# current_sense.net
KiCad netlist of a schematic drawn in EAGLE
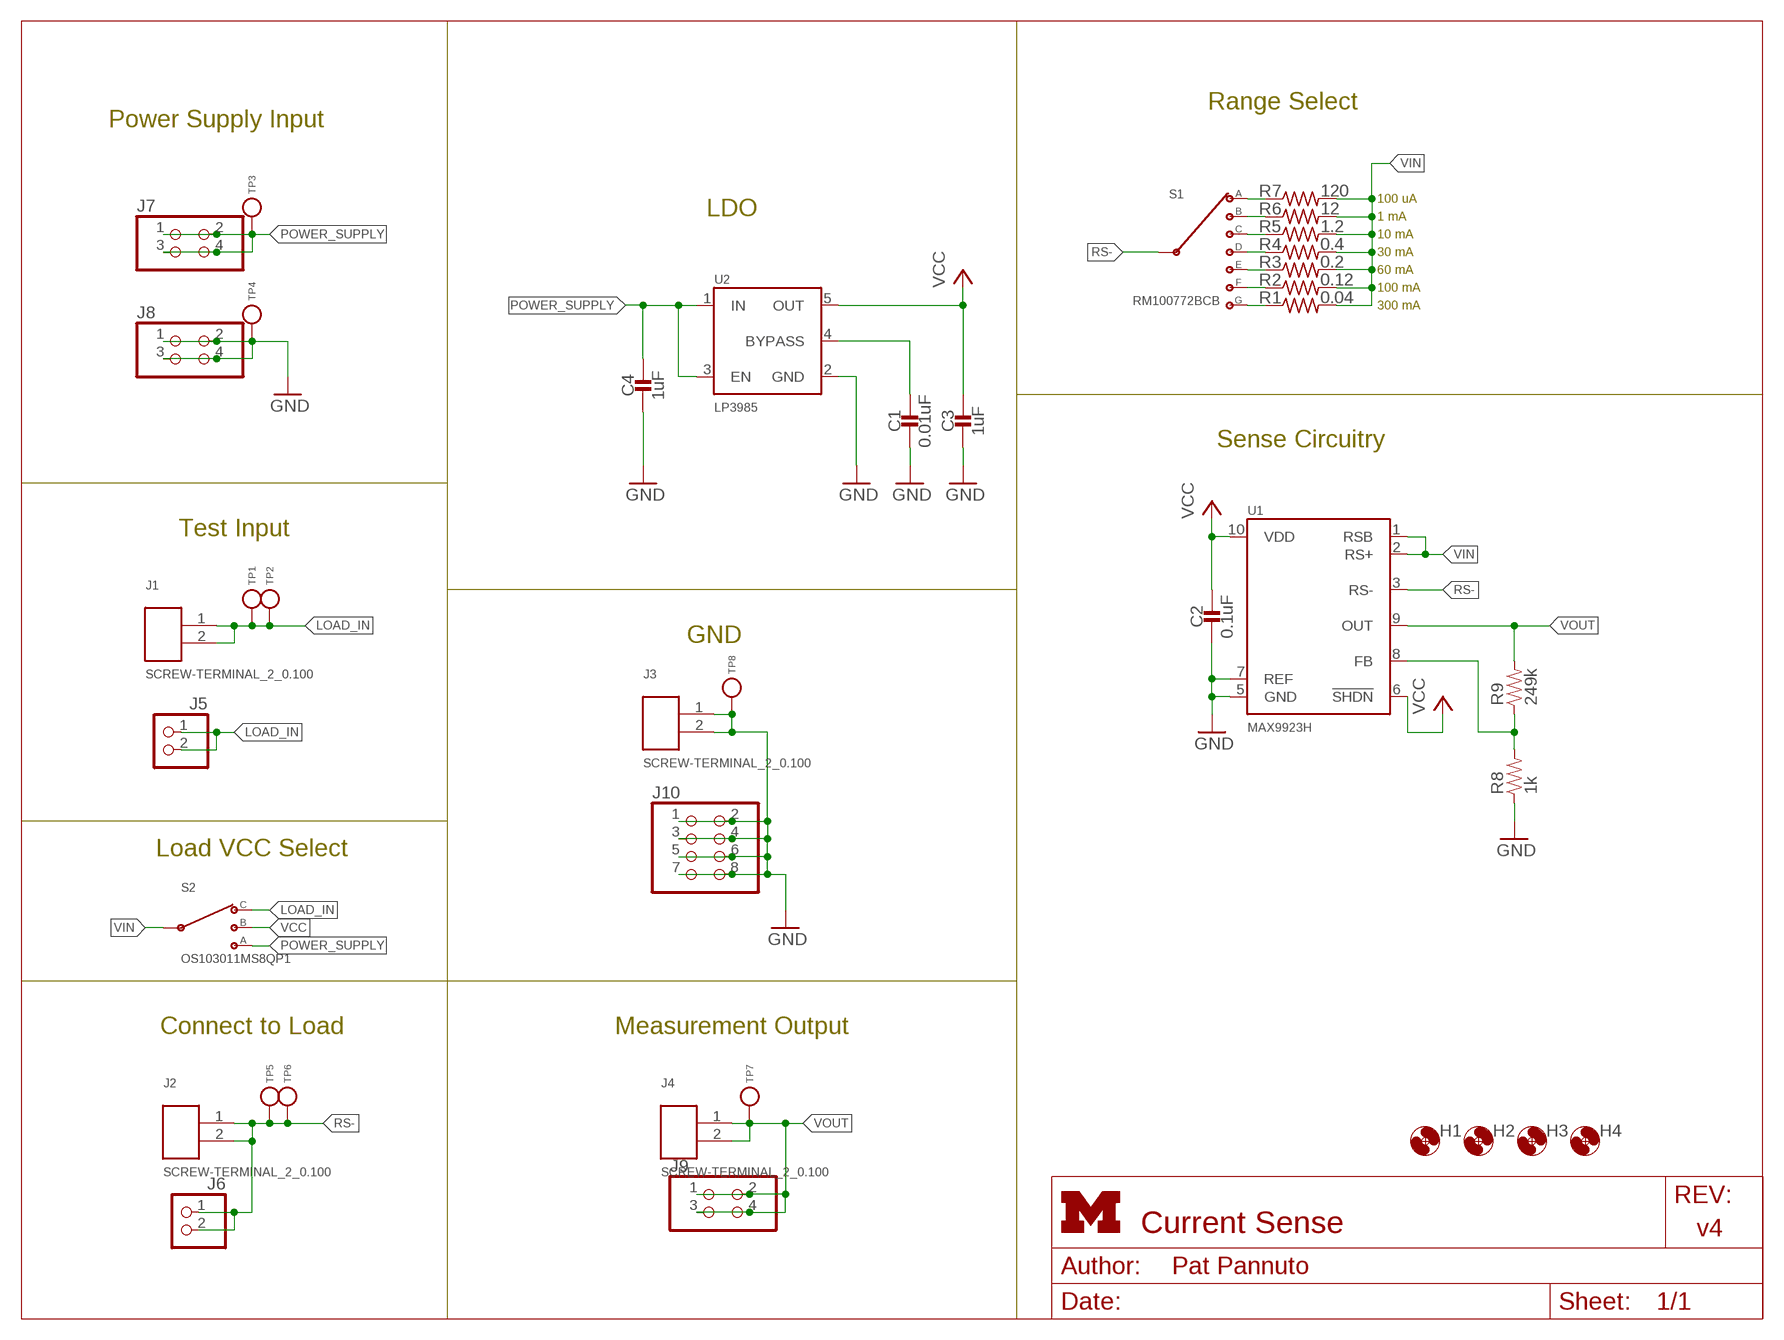
[diagram p0: schematic, sheet 1]

(export (version "E")
  (design (tool "Eeschema 10.0.6"))
  (components
    (comp (ref "C1")
      (value "0.01uF")
      (footprint "eagle-import:0603_CAP")
      (description "CAP CER 10000PF 25V X7R 0603")
      (fields (field (name "MANUFACTURER") "TDK") (field (name "MPN") "C1608X7R1E103K080AA"))
      (libsource (lib "eagle-import") (part "CAPACITOR0603_CAP"))
    )
    (comp (ref "C2")
      (value "0.1uF")
      (footprint "eagle-import:0603_CAP")
      (description "CAP CER .10UF 25V X7R 10% 0603")
      (fields (field (name "MANUFACTURER") "TDK") (field (name "MPN") "C1608X7R1E104K080AA"))
      (libsource (lib "eagle-import") (part "CAPACITOR0603_CAP"))
    )
    (comp (ref "C3")
      (value "1uF")
      (footprint "eagle-import:0603_CAP")
      (description "CAP CER 1UF 16V X7R 0603")
      (fields (field (name "MANUFACTURER") "TDK") (field (name "MPN") "C1608X7R1C105K080AC"))
      (libsource (lib "eagle-import") (part "CAPACITOR0603_CAP"))
    )
    (comp (ref "C4")
      (value "1uF")
      (footprint "eagle-import:0603_CAP")
      (description "CAP CER 1UF 16V X7R 0603")
      (fields (field (name "MANUFACTURER") "TDK") (field (name "MPN") "C1608X7R1C105K080AC"))
      (libsource (lib "eagle-import") (part "CAPACITOR0603_CAP"))
    )
    (comp (ref "H1")
      (value "MOUNT-HOLE3.2")
      (footprint "eagle-import:3,2")
      (libsource (lib "eagle-import") (part "MOUNT-HOLE3.2"))
    )
    (comp (ref "H2")
      (value "MOUNT-HOLE3.2")
      (footprint "eagle-import:3,2")
      (libsource (lib "eagle-import") (part "MOUNT-HOLE3.2"))
    )
    (comp (ref "H3")
      (value "MOUNT-HOLE3.2")
      (footprint "eagle-import:3,2")
      (libsource (lib "eagle-import") (part "MOUNT-HOLE3.2"))
    )
    (comp (ref "H4")
      (value "MOUNT-HOLE3.2")
      (footprint "eagle-import:3,2")
      (libsource (lib "eagle-import") (part "MOUNT-HOLE3.2"))
    )
    (comp (ref "J1")
      (value "SCREW-TERMINAL_2_0.100")
      (footprint "eagle-import:CONN_BLOCK_2")
      (libsource (lib "eagle-import") (part "SCREW-TERMINAL_2_0.100"))
    )
    (comp (ref "J2")
      (value "SCREW-TERMINAL_2_0.100")
      (footprint "eagle-import:CONN_BLOCK_2")
      (libsource (lib "eagle-import") (part "SCREW-TERMINAL_2_0.100"))
    )
    (comp (ref "J3")
      (value "SCREW-TERMINAL_2_0.100")
      (footprint "eagle-import:CONN_BLOCK_2")
      (libsource (lib "eagle-import") (part "SCREW-TERMINAL_2_0.100"))
    )
    (comp (ref "J4")
      (value "SCREW-TERMINAL_2_0.100")
      (footprint "eagle-import:CONN_BLOCK_2")
      (libsource (lib "eagle-import") (part "SCREW-TERMINAL_2_0.100"))
    )
    (comp (ref "J5")
      (value "PINHD-1X2")
      (footprint "eagle-import:1X02")
      (libsource (lib "eagle-import") (part "PINHD-1X2"))
    )
    (comp (ref "J6")
      (value "PINHD-1X2")
      (footprint "eagle-import:1X02")
      (libsource (lib "eagle-import") (part "PINHD-1X2"))
    )
    (comp (ref "J7")
      (value "PINHD-2X2")
      (footprint "eagle-import:2X02")
      (libsource (lib "eagle-import") (part "PINHD-2X2"))
    )
    (comp (ref "J8")
      (value "PINHD-2X2")
      (footprint "eagle-import:2X02")
      (libsource (lib "eagle-import") (part "PINHD-2X2"))
    )
    (comp (ref "J9")
      (value "PINHD-2X2")
      (footprint "eagle-import:2X02")
      (libsource (lib "eagle-import") (part "PINHD-2X2"))
    )
    (comp (ref "J10")
      (value "PINHD-2X4")
      (footprint "eagle-import:2X04")
      (libsource (lib "eagle-import") (part "PINHD-2X4"))
    )
    (comp (ref "R1")
      (value "0.04")
      (footprint "eagle-import:R1206")
      (description "RES 0.04 OHM 1% 1/4W 1206")
      (fields (field (name "MANUFACTURER") "Yageo") (field (name "MPN") "RL1206FR-070R04L"))
      (libsource (lib "eagle-import") (part "R-US_R1206"))
    )
    (comp (ref "R2")
      (value "0.12")
      (footprint "eagle-import:R1206")
      (description "RES 0.12 OHM 1% 1/2W 1206")
      (fields (field (name "MANUFACTURER") "Susumu") (field (name "MPN") "RL1632R-R120-F"))
      (libsource (lib "eagle-import") (part "R-US_R1206"))
    )
    (comp (ref "R3")
      (value "0.2")
      (footprint "eagle-import:R1206")
      (description "RES 0.2 OHM 1% 1/2W 1206")
      (fields (field (name "MANUFACTURER") "Stackpole Electronics") (field (name "MPN") "CSR1206FKR200"))
      (libsource (lib "eagle-import") (part "R-US_R1206"))
    )
    (comp (ref "R4")
      (value "0.4")
      (footprint "eagle-import:R1206")
      (description "RES 0.4 OHM 1% 1/4W 1206")
      (fields (field (name "MANUFACTURER") "Yageo") (field (name "MPN") "RL1206FR-070R4L"))
      (libsource (lib "eagle-import") (part "R-US_R1206"))
    )
    (comp (ref "R5")
      (value "1.2")
      (footprint "eagle-import:R0805")
      (description "RES SMD 1.2 OHM 1% 1/3W 0805")
      (fields (field (name "MANUFACTURER") "Susumu") (field (name "MPN") "RL1220S-1R2-F"))
      (libsource (lib "eagle-import") (part "R-US_R0805"))
    )
    (comp (ref "R6")
      (value "12")
      (footprint "eagle-import:R0805")
      (description "RES SMD 12 OHM 0.1% 1/10W 0805")
      (fields (field (name "MANUFACTURER") "TE Connectivity") (field (name "MPN") "CPF0805B12RE1"))
      (libsource (lib "eagle-import") (part "R-US_R0805"))
    )
    (comp (ref "R7")
      (value "120")
      (footprint "eagle-import:R0805")
      (description "RES SMD 120 OHM 0.05% 1/8W 0805")
      (fields (field (name "MANUFACTURER") "Susumu") (field (name "MPN") "RG2012N-121-W-T1"))
      (libsource (lib "eagle-import") (part "R-US_R0805"))
    )
    (comp (ref "R8")
      (value "1k")
      (footprint "eagle-import:0603-RES")
      (description "RES 1.0K OHM 1/10W .1% 0603 SMD")
      (fields (field (name "MANUFACTURER") "Panasonic") (field (name "MPN") "ERA-3AEB102V"))
      (libsource (lib "eagle-import") (part "RESISTOR0603_RES"))
    )
    (comp (ref "R9")
      (value "249k")
      (footprint "eagle-import:0603-RES")
      (description "RES 249K OHM 1/10W .1% 0603 SMD")
      (fields (field (name "MANUFACTURER") "Panasonic") (field (name "MPN") "ERA-3AEB2493V"))
      (libsource (lib "eagle-import") (part "RESISTOR0603_RES"))
    )
    (comp (ref "S1")
      (value "RM100772BCB")
      (footprint "eagle-import:RM-SWITCH")
      (description "SWITCH ROTARY 7POS 500MA 24V")
      (fields (field (name "MANUFACTURER") "C&K Components") (field (name "MPN") "RM107772BCB"))
      (libsource (lib "eagle-import") (part "RM100772BCB"))
    )
    (comp (ref "S2")
      (value "OS103011MS8QP1")
      (footprint "eagle-import:OS102011MS8QP1")
      (libsource (lib "eagle-import") (part "OS103011MS8QP1"))
    )
    (comp (ref "TP1")
      (value "TEST_POINT_0.040IN")
      (footprint "eagle-import:TESTPOINT_0.040IN")
      (libsource (lib "eagle-import") (part "TEST_POINT_0.040IN"))
    )
    (comp (ref "TP2")
      (value "TEST_POINT_0.040IN")
      (footprint "eagle-import:TESTPOINT_0.040IN")
      (libsource (lib "eagle-import") (part "TEST_POINT_0.040IN"))
    )
    (comp (ref "TP3")
      (value "TEST_POINT_0.040IN")
      (footprint "eagle-import:TESTPOINT_0.040IN")
      (libsource (lib "eagle-import") (part "TEST_POINT_0.040IN"))
    )
    (comp (ref "TP4")
      (value "TEST_POINT_0.040IN")
      (footprint "eagle-import:TESTPOINT_0.040IN")
      (libsource (lib "eagle-import") (part "TEST_POINT_0.040IN"))
    )
    (comp (ref "TP5")
      (value "TEST_POINT_0.040IN")
      (footprint "eagle-import:TESTPOINT_0.040IN")
      (libsource (lib "eagle-import") (part "TEST_POINT_0.040IN"))
    )
    (comp (ref "TP6")
      (value "TEST_POINT_0.040IN")
      (footprint "eagle-import:TESTPOINT_0.040IN")
      (libsource (lib "eagle-import") (part "TEST_POINT_0.040IN"))
    )
    (comp (ref "TP7")
      (value "TEST_POINT_0.040IN")
      (footprint "eagle-import:TESTPOINT_0.040IN")
      (libsource (lib "eagle-import") (part "TEST_POINT_0.040IN"))
    )
    (comp (ref "TP8")
      (value "TEST_POINT_0.112IN")
      (footprint "eagle-import:TESTPOINT_0.112IN")
      (libsource (lib "eagle-import") (part "TEST_POINT_0.112IN"))
    )
    (comp (ref "U1")
      (value "MAX9923H")
      (footprint "eagle-import:UMAX10")
      (description "IC AMP CURRENT SENSE 10-MSOP")
      (fields
        (field (name "DIGIKEY") "MAX9922EUB+TCT-ND")
        (field (name "MANUFACTURER") "Maxim Integrated")
        (field (name "MPN") "MAX9922EUB+T")
      )
      (libsource (lib "eagle-import") (part "MAX9923H"))
    )
    (comp (ref "U2")
      (value "LP3985")
      (footprint "eagle-import:R-PDSO-G5")
      (libsource (lib "eagle-import") (part "LP3985"))
    )
  )
  (nets
    (net (code "1") (name "GND") (class "Default")
      (node (ref "C1") (pin "2") (pinfunction "2_2") (pintype "bidirectional"))
      (node (ref "C2") (pin "2") (pinfunction "2_2") (pintype "bidirectional"))
      (node (ref "C3") (pin "2") (pinfunction "2_2") (pintype "bidirectional"))
      (node (ref "C4") (pin "2") (pinfunction "2_2") (pintype "bidirectional"))
      (node (ref "J10") (pin "1") (pinfunction "1_1") (pintype "passive"))
      (node (ref "J10") (pin "2") (pinfunction "2_2") (pintype "passive"))
      (node (ref "J10") (pin "3") (pinfunction "3_3") (pintype "passive"))
      (node (ref "J10") (pin "4") (pinfunction "4_4") (pintype "passive"))
      (node (ref "J10") (pin "5") (pinfunction "5_5") (pintype "passive"))
      (node (ref "J10") (pin "6") (pinfunction "6_6") (pintype "passive"))
      (node (ref "J10") (pin "7") (pinfunction "7_7") (pintype "passive"))
      (node (ref "J10") (pin "8") (pinfunction "8_8") (pintype "passive"))
      (node (ref "J3") (pin "1") (pinfunction "1_1") (pintype "bidirectional"))
      (node (ref "J3") (pin "2") (pinfunction "2_2") (pintype "bidirectional"))
      (node (ref "J8") (pin "1") (pinfunction "1_1") (pintype "passive"))
      (node (ref "J8") (pin "2") (pinfunction "2_2") (pintype "passive"))
      (node (ref "J8") (pin "3") (pinfunction "3_3") (pintype "passive"))
      (node (ref "J8") (pin "4") (pinfunction "4_4") (pintype "passive"))
      (node (ref "R8") (pin "1") (pinfunction "1_1") (pintype "passive"))
      (node (ref "TP4") (pin "TESTPOINT") (pinfunction "TESTPOINT_TESTPOINT") (pintype "bidirectional"))
      (node (ref "TP8") (pin "1") (pinfunction "TESTPOINT_1") (pintype "bidirectional"))
      (node (ref "U1") (pin "5") (pinfunction "GND_5") (pintype "bidirectional"))
      (node (ref "U1") (pin "7") (pinfunction "REF_7") (pintype "bidirectional"))
      (node (ref "U2") (pin "2") (pinfunction "GND_2") (pintype "bidirectional"))
    )
    (net (code "2") (name "LOAD_IN") (class "Default")
      (node (ref "J1") (pin "1") (pinfunction "1_1") (pintype "bidirectional"))
      (node (ref "J1") (pin "2") (pinfunction "2_2") (pintype "bidirectional"))
      (node (ref "J5") (pin "1") (pinfunction "1_1") (pintype "passive"))
      (node (ref "J5") (pin "2") (pinfunction "2_2") (pintype "passive"))
      (node (ref "S2") (pin "4") (pinfunction "3_4") (pintype "bidirectional"))
      (node (ref "TP1") (pin "TESTPOINT") (pinfunction "TESTPOINT_TESTPOINT") (pintype "bidirectional"))
      (node (ref "TP2") (pin "TESTPOINT") (pinfunction "TESTPOINT_TESTPOINT") (pintype "bidirectional"))
    )
    (net (code "3") (name "Net-(S1-A)") (class "Default")
      (node (ref "R7") (pin "1") (pinfunction "1_1") (pintype "passive"))
      (node (ref "S1") (pin "1") (pinfunction "A_1") (pintype "bidirectional"))
    )
    (net (code "4") (name "Net-(S1-B)") (class "Default")
      (node (ref "R6") (pin "1") (pinfunction "1_1") (pintype "passive"))
      (node (ref "S1") (pin "2") (pinfunction "B_2") (pintype "bidirectional"))
    )
    (net (code "5") (name "Net-(S1-C)") (class "Default")
      (node (ref "R5") (pin "1") (pinfunction "1_1") (pintype "passive"))
      (node (ref "S1") (pin "3") (pinfunction "C_3") (pintype "bidirectional"))
    )
    (net (code "6") (name "Net-(S1-D)") (class "Default")
      (node (ref "R4") (pin "1") (pinfunction "1_1") (pintype "passive"))
      (node (ref "S1") (pin "4") (pinfunction "D_4") (pintype "bidirectional"))
    )
    (net (code "7") (name "Net-(S1-E)") (class "Default")
      (node (ref "R3") (pin "1") (pinfunction "1_1") (pintype "passive"))
      (node (ref "S1") (pin "5") (pinfunction "E_5") (pintype "bidirectional"))
    )
    (net (code "8") (name "Net-(S1-F)") (class "Default")
      (node (ref "R2") (pin "1") (pinfunction "1_1") (pintype "passive"))
      (node (ref "S1") (pin "6") (pinfunction "F_6") (pintype "bidirectional"))
    )
    (net (code "9") (name "Net-(S1-G)") (class "Default")
      (node (ref "R1") (pin "1") (pinfunction "1_1") (pintype "passive"))
      (node (ref "S1") (pin "7") (pinfunction "G_7") (pintype "bidirectional"))
    )
    (net (code "10") (name "Net-(U1-FB)") (class "Default")
      (node (ref "R8") (pin "2") (pinfunction "2_2") (pintype "passive"))
      (node (ref "R9") (pin "1") (pinfunction "1_1") (pintype "passive"))
      (node (ref "U1") (pin "8") (pinfunction "FB_8") (pintype "bidirectional"))
    )
    (net (code "11") (name "Net-(U2-BYPASS)") (class "Default")
      (node (ref "C1") (pin "1") (pinfunction "1_1") (pintype "bidirectional"))
      (node (ref "U2") (pin "4") (pinfunction "BYPASS_4") (pintype "bidirectional"))
    )
    (net (code "12") (name "POWER_SUPPLY") (class "Default")
      (node (ref "C4") (pin "1") (pinfunction "1_1") (pintype "bidirectional"))
      (node (ref "J7") (pin "1") (pinfunction "1_1") (pintype "passive"))
      (node (ref "J7") (pin "2") (pinfunction "2_2") (pintype "passive"))
      (node (ref "J7") (pin "3") (pinfunction "3_3") (pintype "passive"))
      (node (ref "J7") (pin "4") (pinfunction "4_4") (pintype "passive"))
      (node (ref "S2") (pin "1") (pinfunction "1_1") (pintype "bidirectional"))
      (node (ref "TP3") (pin "TESTPOINT") (pinfunction "TESTPOINT_TESTPOINT") (pintype "bidirectional"))
      (node (ref "U2") (pin "1") (pinfunction "IN_1") (pintype "bidirectional"))
      (node (ref "U2") (pin "3") (pinfunction "EN_3") (pintype "bidirectional"))
    )
    (net (code "13") (name "RS-") (class "Default")
      (node (ref "J2") (pin "1") (pinfunction "1_1") (pintype "bidirectional"))
      (node (ref "J2") (pin "2") (pinfunction "2_2") (pintype "bidirectional"))
      (node (ref "J6") (pin "1") (pinfunction "1_1") (pintype "passive"))
      (node (ref "J6") (pin "2") (pinfunction "2_2") (pintype "passive"))
      (node (ref "S1") (pin "C") (pinfunction "INPUT_C") (pintype "bidirectional"))
      (node (ref "TP5") (pin "TESTPOINT") (pinfunction "TESTPOINT_TESTPOINT") (pintype "bidirectional"))
      (node (ref "TP6") (pin "TESTPOINT") (pinfunction "TESTPOINT_TESTPOINT") (pintype "bidirectional"))
      (node (ref "U1") (pin "3") (pinfunction "RS-_3") (pintype "bidirectional"))
    )
    (net (code "14") (name "VCC") (class "Default")
      (node (ref "C2") (pin "1") (pinfunction "1_1") (pintype "bidirectional"))
      (node (ref "C3") (pin "1") (pinfunction "1_1") (pintype "bidirectional"))
      (node (ref "S2") (pin "3") (pinfunction "2_3") (pintype "bidirectional"))
      (node (ref "U1") (pin "10") (pinfunction "VDD_10") (pintype "bidirectional"))
      (node (ref "U1") (pin "6") (pinfunction "~{SHDN}_6") (pintype "bidirectional"))
      (node (ref "U2") (pin "5") (pinfunction "OUT_5") (pintype "bidirectional"))
    )
    (net (code "15") (name "VIN") (class "Default")
      (node (ref "R1") (pin "2") (pinfunction "2_2") (pintype "passive"))
      (node (ref "R2") (pin "2") (pinfunction "2_2") (pintype "passive"))
      (node (ref "R3") (pin "2") (pinfunction "2_2") (pintype "passive"))
      (node (ref "R4") (pin "2") (pinfunction "2_2") (pintype "passive"))
      (node (ref "R5") (pin "2") (pinfunction "2_2") (pintype "passive"))
      (node (ref "R6") (pin "2") (pinfunction "2_2") (pintype "passive"))
      (node (ref "R7") (pin "2") (pinfunction "2_2") (pintype "passive"))
      (node (ref "S2") (pin "2") (pinfunction "C_2") (pintype "bidirectional"))
      (node (ref "U1") (pin "1") (pinfunction "RSB_1") (pintype "bidirectional"))
      (node (ref "U1") (pin "2") (pinfunction "RS+_2") (pintype "bidirectional"))
    )
    (net (code "16") (name "VOUT") (class "Default")
      (node (ref "J4") (pin "1") (pinfunction "1_1") (pintype "bidirectional"))
      (node (ref "J4") (pin "2") (pinfunction "2_2") (pintype "bidirectional"))
      (node (ref "J9") (pin "1") (pinfunction "1_1") (pintype "passive"))
      (node (ref "J9") (pin "2") (pinfunction "2_2") (pintype "passive"))
      (node (ref "J9") (pin "3") (pinfunction "3_3") (pintype "passive"))
      (node (ref "J9") (pin "4") (pinfunction "4_4") (pintype "passive"))
      (node (ref "R9") (pin "2") (pinfunction "2_2") (pintype "passive"))
      (node (ref "TP7") (pin "TESTPOINT") (pinfunction "TESTPOINT_TESTPOINT") (pintype "bidirectional"))
      (node (ref "U1") (pin "9") (pinfunction "OUT_9") (pintype "bidirectional"))
    )
  )
)
